# power_supply.net
KiCad netlist of a schematic drawn in Altium Designer
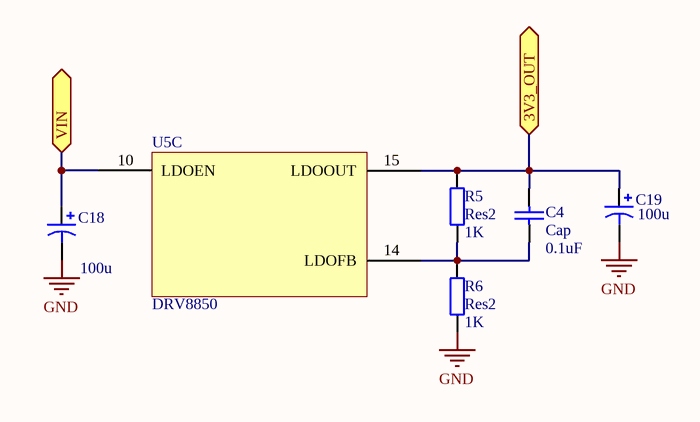
[diagram p0: power_supply.SchDoc]

(export (version "E")
  (design (tool "Eeschema 10.0.6"))
  (components
    (comp (ref "C4")
      (value "Cap")
      (footprint "RAD-0.3")
      (description "Capacitor")
      (fields (field (name "ALTIUM_VALUE") "0.1uF") (field (name "PUBLISHER") "Altium Limited"))
      (libsource (lib "Miscellaneous Devices") (part "Cap"))
    )
    (comp (ref "C18")
      (value "100u")
      (footprint "Tantalum_cap_D")
      (description "Polarized Capacitor (Radial)")
      (fields (field (name "PUBLISHER") "Altium Limited"))
      (libsource (lib "Miscellaneous Devices") (part "Cap Pol1"))
    )
    (comp (ref "C19")
      (value "100u")
      (footprint "Tantalum_cap_D")
      (description "Polarized Capacitor (Radial)")
      (fields (field (name "PUBLISHER") "Altium Limited"))
      (libsource (lib "Miscellaneous Devices") (part "Cap Pol1"))
    )
    (comp (ref "R5")
      (value "Res2")
      (footprint "AXIAL-0.4")
      (description "Resistor")
      (fields (field (name "ALTIUM_VALUE") "1K") (field (name "PUBLISHER") "Altium Limited"))
      (libsource (lib "Miscellaneous Devices") (part "Res2"))
    )
    (comp (ref "R6")
      (value "Res2")
      (footprint "AXIAL-0.4")
      (description "Resistor")
      (fields (field (name "ALTIUM_VALUE") "1K") (field (name "PUBLISHER") "Altium Limited"))
      (libsource (lib "Miscellaneous Devices") (part "Res2"))
    )
    (comp (ref "U5") (value "DRV8850") (libsource (lib "motee_v2") (part "DRV8850")))
  )
  (nets
    (net (code "1") (name "/3V3_OUT") (class "Default")
      (node (ref "C19") (pin "1") (pinfunction "1_1") (pintype "passive"))
      (node (ref "C4") (pin "2") (pinfunction "2_2") (pintype "passive"))
      (node (ref "R5") (pin "2") (pinfunction "2_2") (pintype "passive"))
      (node (ref "U5") (pin "15") (pinfunction "LDOOUT_15") (pintype "passive"))
    )
    (net (code "2") (name "/VIN") (class "Default")
      (node (ref "C18") (pin "1") (pinfunction "1_1") (pintype "passive"))
      (node (ref "U5") (pin "10") (pinfunction "LDOEN_10") (pintype "passive"))
    )
    (net (code "3") (name "GND") (class "Default")
      (node (ref "C18") (pin "2") (pinfunction "2_2") (pintype "passive"))
      (node (ref "C19") (pin "2") (pinfunction "2_2") (pintype "passive"))
      (node (ref "R6") (pin "1") (pinfunction "1_1") (pintype "passive"))
    )
    (net (code "4") (name "Net-(U5C-LDOFB)") (class "Default")
      (node (ref "C4") (pin "1") (pinfunction "1_1") (pintype "passive"))
      (node (ref "R5") (pin "1") (pinfunction "1_1") (pintype "passive"))
      (node (ref "R6") (pin "2") (pinfunction "2_2") (pintype "passive"))
      (node (ref "U5") (pin "14") (pinfunction "LDOFB_14") (pintype "passive"))
    )
  )
)
